# MCLR.net
KiCad netlist of a schematic drawn in Altium Designer
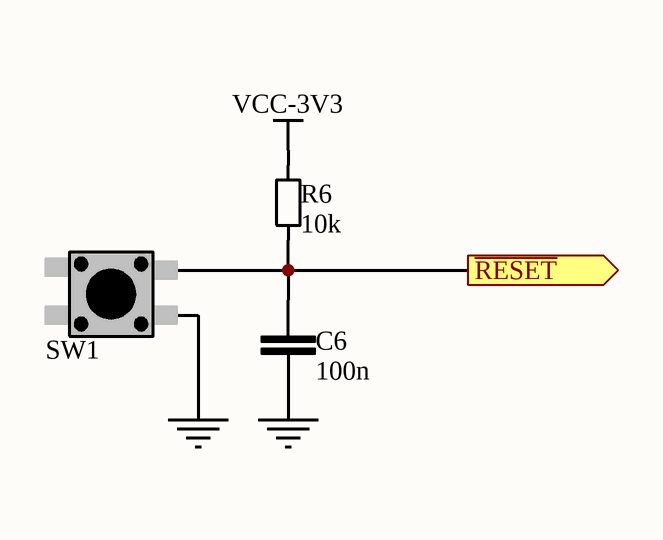
[diagram p0: MCLR.SchDoc]

(export (version "E")
  (design (tool "Eeschema 10.0.6"))
  (components
    (comp (ref "C6")
      (value "100n")
      (footprint "CER_0603")
      (description "CAP CER 100n 10V X5R 10% 0603")
      (libsource (lib "Capacitors") (part "06032105"))
    )
    (comp (ref "R6")
      (value "10k")
      (footprint "RESC2013X38N-0805-NOOVERLAY")
      (description "RES SMD 10 kOhm 1/8W 0805")
      (libsource (lib "Resistors") (part "000001002"))
    )
    (comp (ref "SW1")
      (value "TASTER")
      (footprint "TASTER_SMD")
      (libsource (lib "Electro_Mechanical") (part "TASTER"))
    )
  )
  (nets
    (net (code "1") (name "/~{RESET}") (class "Default")
      (node (ref "C6") (pin "2") (pinfunction "2_2") (pintype "passive"))
      (node (ref "R6") (pin "1") (pinfunction "1_1") (pintype "passive"))
      (node (ref "SW1") (pin "2") (pinfunction "2_2") (pintype "passive"))
    )
    (net (code "2") (name "GND") (class "Default")
      (node (ref "C6") (pin "1") (pinfunction "1_1") (pintype "passive"))
      (node (ref "SW1") (pin "1") (pinfunction "1_1") (pintype "passive"))
    )
    (net (code "3") (name "VCC-3V3") (class "Default")
      (node (ref "R6") (pin "2") (pinfunction "2_2") (pintype "passive"))
    )
  )
)
